# S2Mn10.net
KiCad netlist of a schematic drawn in EAGLE
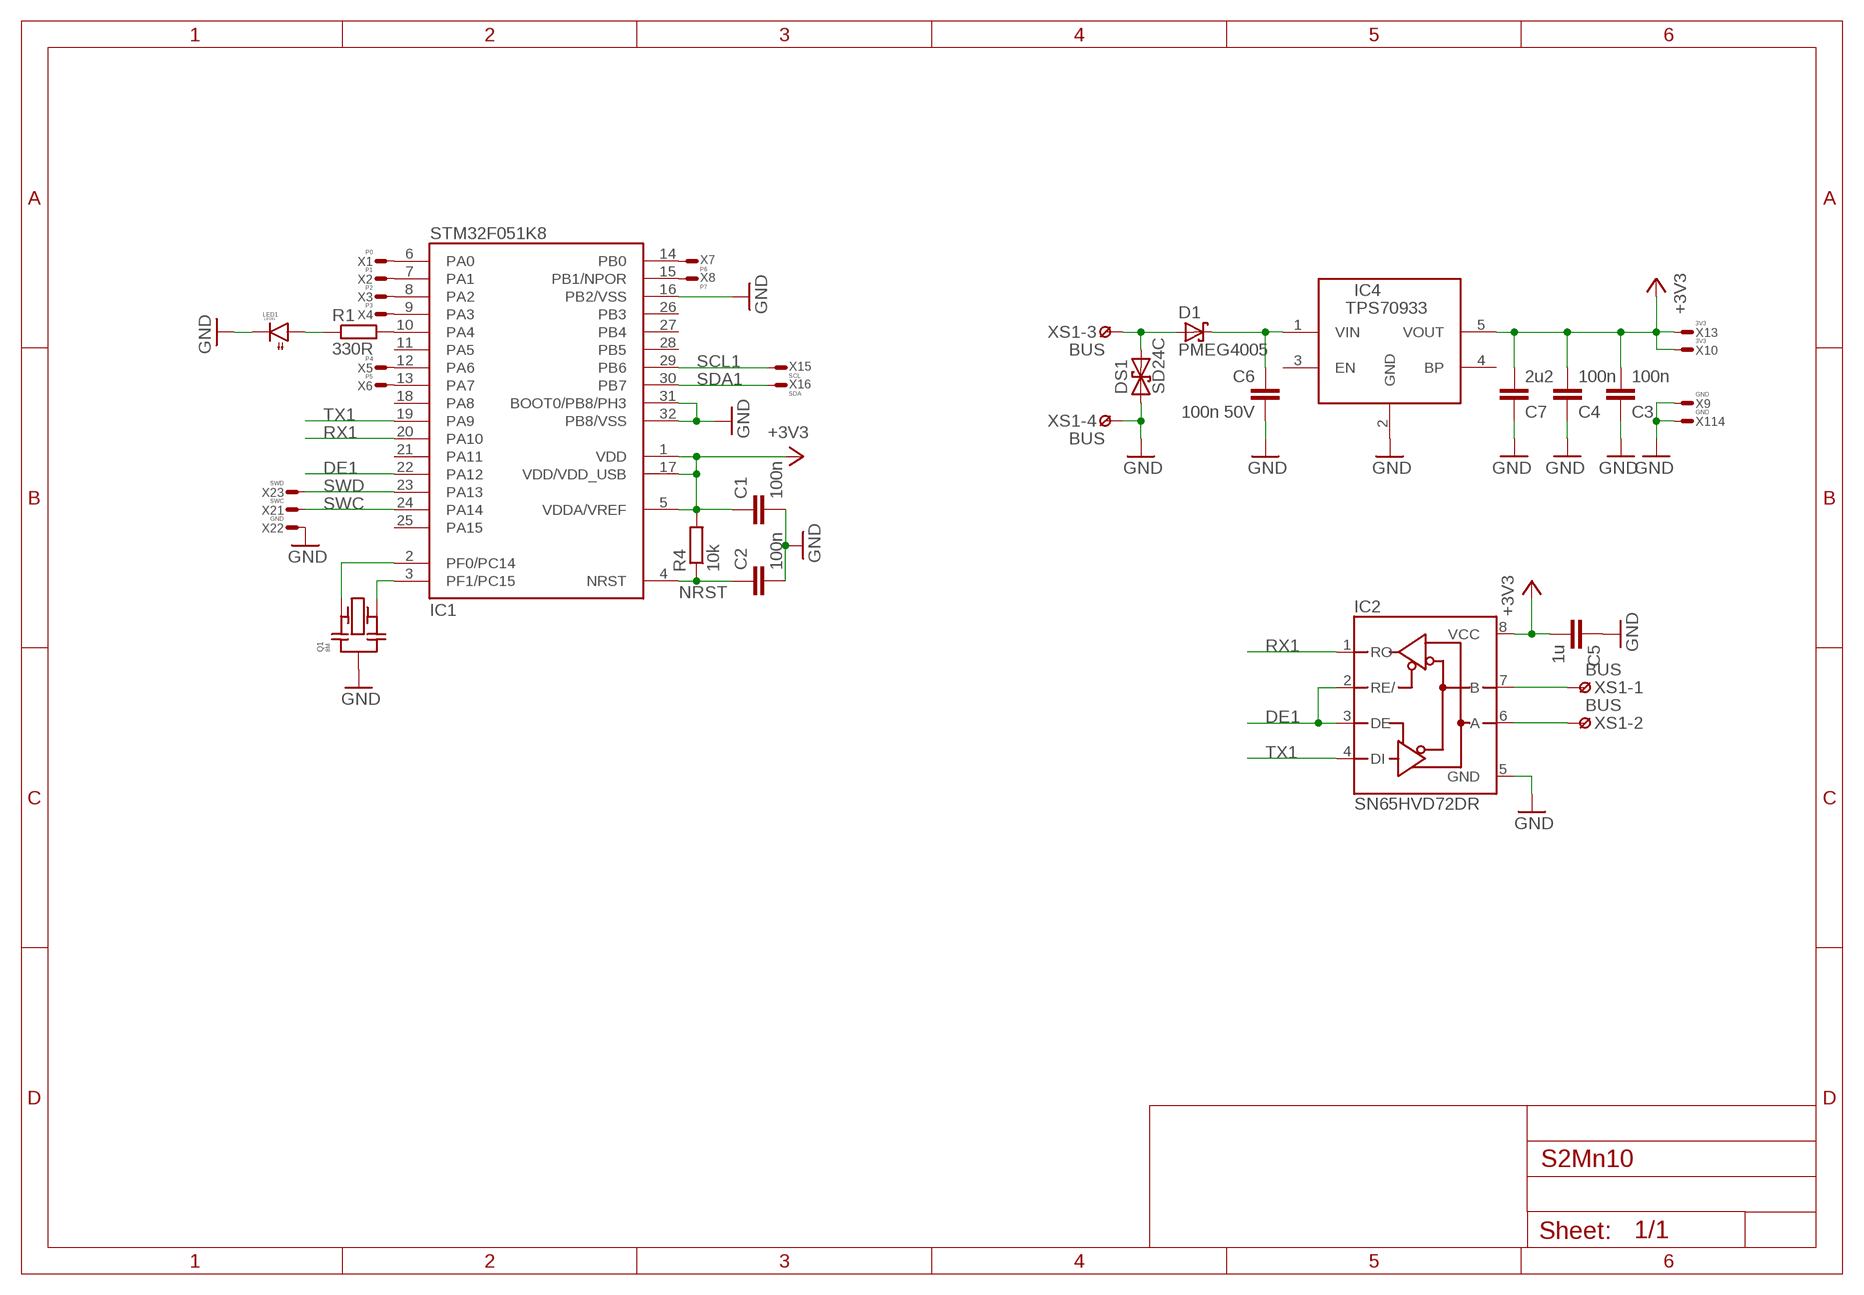
[diagram p0: schematic, sheet 1]

(export (version "E")
  (design (tool "Eeschema 10.0.6"))
  (components
    (comp (ref "C1")
      (value "100n")
      (footprint "eagle-import:0603")
      (libsource (lib "eagle-import") (part "C0603"))
    )
    (comp (ref "C2")
      (value "100n")
      (footprint "eagle-import:0603")
      (libsource (lib "eagle-import") (part "C0603"))
    )
    (comp (ref "C3")
      (value "100n")
      (footprint "eagle-import:0603")
      (libsource (lib "eagle-import") (part "C0603"))
    )
    (comp (ref "C4")
      (value "100n")
      (footprint "eagle-import:0603")
      (libsource (lib "eagle-import") (part "C0603"))
    )
    (comp (ref "C5")
      (value "1u")
      (footprint "eagle-import:0603")
      (libsource (lib "eagle-import") (part "C0603"))
    )
    (comp (ref "C6")
      (value "100n 50V")
      (footprint "eagle-import:0603")
      (libsource (lib "eagle-import") (part "C0603"))
    )
    (comp (ref "C7")
      (value "2u2")
      (footprint "eagle-import:0603")
      (libsource (lib "eagle-import") (part "C0603"))
    )
    (comp (ref "D1")
      (value "PMEG4005")
      (footprint "eagle-import:SOD323")
      (libsource (lib "eagle-import") (part "D-SCHOTKY323"))
    )
    (comp (ref "DS1")
      (value "SD24C")
      (footprint "eagle-import:SOD323")
      (libsource (lib "eagle-import") (part "TVS-U323"))
    )
    (comp (ref "IC1")
      (value "STM32F051K8")
      (footprint "eagle-import:LQFP32-7X7")
      (libsource (lib "eagle-import") (part "STM32_LQFP32"))
    )
    (comp (ref "IC2")
      (value "SN65HVD72DR")
      (footprint "eagle-import:SOIC8")
      (libsource (lib "eagle-import") (part "MAX485"))
    )
    (comp (ref "IC4")
      (value "TPS70933")
      (footprint "eagle-import:SOT23-5")
      (libsource (lib "eagle-import") (part "LDO"))
    )
    (comp (ref "LED1")
      (value "LEDG")
      (footprint "eagle-import:1206")
      (libsource (lib "eagle-import") (part "LED1206"))
    )
    (comp (ref "Q1")
      (value "8M")
      (footprint "eagle-import:CSTCE")
      (libsource (lib "eagle-import") (part "QRCE"))
    )
    (comp (ref "R1")
      (value "330R")
      (footprint "eagle-import:0603")
      (libsource (lib "eagle-import") (part "R0603"))
    )
    (comp (ref "R4")
      (value "10k")
      (footprint "eagle-import:0603")
      (libsource (lib "eagle-import") (part "R0603"))
    )
    (comp (ref "X1")
      (value "P0")
      (footprint "eagle-import:T1.6_0.9")
      (libsource (lib "eagle-import") (part "WIREPADT1.6/0.9"))
    )
    (comp (ref "X2")
      (value "P1")
      (footprint "eagle-import:T1.6_0.9")
      (libsource (lib "eagle-import") (part "WIREPADT1.6/0.9"))
    )
    (comp (ref "X3")
      (value "P2")
      (footprint "eagle-import:T1.6_0.9")
      (libsource (lib "eagle-import") (part "WIREPADT1.6/0.9"))
    )
    (comp (ref "X4")
      (value "P3")
      (footprint "eagle-import:T1.6_0.9")
      (libsource (lib "eagle-import") (part "WIREPADT1.6/0.9"))
    )
    (comp (ref "X5")
      (value "P4")
      (footprint "eagle-import:T1.6_0.9")
      (libsource (lib "eagle-import") (part "WIREPADT1.6/0.9"))
    )
    (comp (ref "X6")
      (value "P5")
      (footprint "eagle-import:T1.6_0.9")
      (libsource (lib "eagle-import") (part "WIREPADT1.6/0.9"))
    )
    (comp (ref "X7")
      (value "P6")
      (footprint "eagle-import:T1.6_0.9")
      (libsource (lib "eagle-import") (part "WIREPADT1.6/0.9"))
    )
    (comp (ref "X8")
      (value "P7")
      (footprint "eagle-import:T1.6_0.9")
      (libsource (lib "eagle-import") (part "WIREPADT1.6/0.9"))
    )
    (comp (ref "X9")
      (value "GND")
      (footprint "eagle-import:T1.6_0.9")
      (libsource (lib "eagle-import") (part "WIREPADT1.6/0.9"))
    )
    (comp (ref "X10")
      (value "3V3")
      (footprint "eagle-import:T1.6_0.9")
      (libsource (lib "eagle-import") (part "WIREPADT1.6/0.9"))
    )
    (comp (ref "X13")
      (value "3V3")
      (footprint "eagle-import:T1.6_0.9")
      (libsource (lib "eagle-import") (part "WIREPADT1.6/0.9"))
    )
    (comp (ref "X15")
      (value "SCL")
      (footprint "eagle-import:T1.6_0.9")
      (libsource (lib "eagle-import") (part "WIREPADT1.6/0.9"))
    )
    (comp (ref "X16")
      (value "SDA")
      (footprint "eagle-import:T1.6_0.9")
      (libsource (lib "eagle-import") (part "WIREPADT1.6/0.9"))
    )
    (comp (ref "X21")
      (value "SWC")
      (footprint "eagle-import:T1.6_0.9")
      (libsource (lib "eagle-import") (part "WIREPADT1.6/0.9"))
    )
    (comp (ref "X22")
      (value "GND")
      (footprint "eagle-import:T1.6_0.9")
      (libsource (lib "eagle-import") (part "WIREPADT1.6/0.9"))
    )
    (comp (ref "X23")
      (value "SWD")
      (footprint "eagle-import:T1.6_0.9")
      (libsource (lib "eagle-import") (part "WIREPADT1.6/0.9"))
    )
    (comp (ref "X114")
      (value "GND")
      (footprint "eagle-import:T1.6_0.9")
      (libsource (lib "eagle-import") (part "WIREPADT1.6/0.9"))
    )
    (comp (ref "XS1")
      (value "BUS")
      (footprint "eagle-import:1725672")
      (libsource (lib "eagle-import") (part "1725672"))
    )
  )
  (nets
    (net (code "1") (name "+3V3") (class "Default")
      (node (ref "C1") (pin "1") (pinfunction "1_1") (pintype "passive"))
      (node (ref "C3") (pin "2") (pinfunction "2_2") (pintype "passive"))
      (node (ref "C4") (pin "2") (pinfunction "2_2") (pintype "passive"))
      (node (ref "C5") (pin "2") (pinfunction "2_2") (pintype "passive"))
      (node (ref "C7") (pin "2") (pinfunction "2_2") (pintype "passive"))
      (node (ref "IC1") (pin "1") (pinfunction "VDD_1") (pintype "bidirectional"))
      (node (ref "IC1") (pin "17") (pinfunction "VDD/VDD_USB_17") (pintype "bidirectional"))
      (node (ref "IC1") (pin "5") (pinfunction "VDDA/VREF_5") (pintype "bidirectional"))
      (node (ref "IC2") (pin "8") (pinfunction "VCC_8") (pintype "bidirectional"))
      (node (ref "IC4") (pin "5") (pinfunction "VOUT_5") (pintype "bidirectional"))
      (node (ref "R4") (pin "2") (pinfunction "2_2") (pintype "passive"))
      (node (ref "X10") (pin "1") (pinfunction "S_1") (pintype "passive"))
      (node (ref "X13") (pin "1") (pinfunction "S_1") (pintype "passive"))
    )
    (net (code "2") (name "/DE1") (class "Default")
      (node (ref "IC1") (pin "22") (pinfunction "PA12_22") (pintype "bidirectional"))
      (node (ref "IC2") (pin "2") (pinfunction "RE/_2") (pintype "bidirectional"))
      (node (ref "IC2") (pin "3") (pinfunction "DE_3") (pintype "bidirectional"))
    )
    (net (code "3") (name "/NRST") (class "Default")
      (node (ref "C2") (pin "1") (pinfunction "1_1") (pintype "passive"))
      (node (ref "IC1") (pin "4") (pinfunction "NRST_4") (pintype "bidirectional"))
      (node (ref "R4") (pin "1") (pinfunction "1_1") (pintype "passive"))
    )
    (net (code "4") (name "/RX1") (class "Default")
      (node (ref "IC1") (pin "20") (pinfunction "PA10_20") (pintype "bidirectional"))
      (node (ref "IC2") (pin "1") (pinfunction "RO_1") (pintype "bidirectional"))
    )
    (net (code "5") (name "/SCL1") (class "Default")
      (node (ref "IC1") (pin "29") (pinfunction "PB6_29") (pintype "bidirectional"))
      (node (ref "X15") (pin "1") (pinfunction "S_1") (pintype "passive"))
    )
    (net (code "6") (name "/SDA1") (class "Default")
      (node (ref "IC1") (pin "30") (pinfunction "PB7_30") (pintype "bidirectional"))
      (node (ref "X16") (pin "1") (pinfunction "S_1") (pintype "passive"))
    )
    (net (code "7") (name "/SWC") (class "Default")
      (node (ref "IC1") (pin "24") (pinfunction "PA14_24") (pintype "bidirectional"))
      (node (ref "X21") (pin "1") (pinfunction "S_1") (pintype "passive"))
    )
    (net (code "8") (name "/SWD") (class "Default")
      (node (ref "IC1") (pin "23") (pinfunction "PA13_23") (pintype "bidirectional"))
      (node (ref "X23") (pin "1") (pinfunction "S_1") (pintype "passive"))
    )
    (net (code "9") (name "/TX1") (class "Default")
      (node (ref "IC1") (pin "19") (pinfunction "PA9_19") (pintype "bidirectional"))
      (node (ref "IC2") (pin "4") (pinfunction "DI_4") (pintype "bidirectional"))
    )
    (net (code "10") (name "GND") (class "Default")
      (node (ref "C1") (pin "2") (pinfunction "2_2") (pintype "passive"))
      (node (ref "C2") (pin "2") (pinfunction "2_2") (pintype "passive"))
      (node (ref "C3") (pin "1") (pinfunction "1_1") (pintype "passive"))
      (node (ref "C4") (pin "1") (pinfunction "1_1") (pintype "passive"))
      (node (ref "C5") (pin "1") (pinfunction "1_1") (pintype "passive"))
      (node (ref "C6") (pin "2") (pinfunction "2_2") (pintype "passive"))
      (node (ref "C7") (pin "1") (pinfunction "1_1") (pintype "passive"))
      (node (ref "DS1") (pin "A") (pinfunction "1_A") (pintype "passive"))
      (node (ref "IC1") (pin "16") (pinfunction "PB2/VSS_16") (pintype "bidirectional"))
      (node (ref "IC1") (pin "31") (pinfunction "BOOT0/PB8/PH3_31") (pintype "bidirectional"))
      (node (ref "IC1") (pin "32") (pinfunction "PB8/VSS_32") (pintype "bidirectional"))
      (node (ref "IC2") (pin "5") (pinfunction "GND_5") (pintype "bidirectional"))
      (node (ref "IC4") (pin "2") (pinfunction "GND_2") (pintype "bidirectional"))
      (node (ref "LED1") (pin "2") (pinfunction "C_2") (pintype "bidirectional"))
      (node (ref "Q1") (pin "G") (pinfunction "M_G") (pintype "passive"))
      (node (ref "X114") (pin "1") (pinfunction "S_1") (pintype "passive"))
      (node (ref "X22") (pin "1") (pinfunction "S_1") (pintype "passive"))
      (node (ref "X9") (pin "1") (pinfunction "S_1") (pintype "passive"))
      (node (ref "XS1") (pin "4") (pinfunction "K_4") (pintype "passive"))
    )
    (net (code "11") (name "Net-(DS1-2)") (class "Default")
      (node (ref "D1") (pin "A") (pinfunction "A_A") (pintype "passive"))
      (node (ref "DS1") (pin "C") (pinfunction "2_C") (pintype "passive"))
      (node (ref "XS1") (pin "3") (pinfunction "K_3") (pintype "passive"))
    )
    (net (code "12") (name "Net-(IC1-PA0)") (class "Default")
      (node (ref "IC1") (pin "6") (pinfunction "PA0_6") (pintype "bidirectional"))
      (node (ref "X1") (pin "1") (pinfunction "S_1") (pintype "passive"))
    )
    (net (code "13") (name "Net-(IC1-PA1)") (class "Default")
      (node (ref "IC1") (pin "7") (pinfunction "PA1_7") (pintype "bidirectional"))
      (node (ref "X2") (pin "1") (pinfunction "S_1") (pintype "passive"))
    )
    (net (code "14") (name "Net-(IC1-PA2)") (class "Default")
      (node (ref "IC1") (pin "8") (pinfunction "PA2_8") (pintype "bidirectional"))
      (node (ref "X3") (pin "1") (pinfunction "S_1") (pintype "passive"))
    )
    (net (code "15") (name "Net-(IC1-PA3)") (class "Default")
      (node (ref "IC1") (pin "9") (pinfunction "PA3_9") (pintype "bidirectional"))
      (node (ref "X4") (pin "1") (pinfunction "S_1") (pintype "passive"))
    )
    (net (code "16") (name "Net-(IC1-PA4)") (class "Default")
      (node (ref "IC1") (pin "10") (pinfunction "PA4_10") (pintype "bidirectional"))
      (node (ref "R1") (pin "2") (pinfunction "2_2") (pintype "passive"))
    )
    (net (code "17") (name "Net-(IC1-PA6)") (class "Default")
      (node (ref "IC1") (pin "12") (pinfunction "PA6_12") (pintype "bidirectional"))
      (node (ref "X5") (pin "1") (pinfunction "S_1") (pintype "passive"))
    )
    (net (code "18") (name "Net-(IC1-PA7)") (class "Default")
      (node (ref "IC1") (pin "13") (pinfunction "PA7_13") (pintype "bidirectional"))
      (node (ref "X6") (pin "1") (pinfunction "S_1") (pintype "passive"))
    )
    (net (code "19") (name "Net-(IC1-PB0)") (class "Default")
      (node (ref "IC1") (pin "14") (pinfunction "PB0_14") (pintype "bidirectional"))
      (node (ref "X7") (pin "1") (pinfunction "S_1") (pintype "passive"))
    )
    (net (code "20") (name "Net-(IC1-PB1{slash}NPOR)") (class "Default")
      (node (ref "IC1") (pin "15") (pinfunction "PB1/NPOR_15") (pintype "bidirectional"))
      (node (ref "X8") (pin "1") (pinfunction "S_1") (pintype "passive"))
    )
    (net (code "21") (name "Net-(IC1-PF0{slash}PC14)") (class "Default")
      (node (ref "IC1") (pin "2") (pinfunction "PF0/PC14_2") (pintype "bidirectional"))
      (node (ref "Q1") (pin "A") (pinfunction "1_A") (pintype "passive"))
    )
    (net (code "22") (name "Net-(IC1-PF1{slash}PC15)") (class "Default")
      (node (ref "IC1") (pin "3") (pinfunction "PF1/PC15_3") (pintype "bidirectional"))
      (node (ref "Q1") (pin "B") (pinfunction "2_B") (pintype "passive"))
    )
    (net (code "23") (name "Net-(IC2-A)") (class "Default")
      (node (ref "IC2") (pin "6") (pinfunction "A_6") (pintype "bidirectional"))
      (node (ref "XS1") (pin "2") (pinfunction "K_2") (pintype "passive"))
    )
    (net (code "24") (name "Net-(IC2-B)") (class "Default")
      (node (ref "IC2") (pin "7") (pinfunction "B_7") (pintype "bidirectional"))
      (node (ref "XS1") (pin "1") (pinfunction "K_1") (pintype "passive"))
    )
    (net (code "25") (name "Net-(IC4-VIN)") (class "Default")
      (node (ref "C6") (pin "1") (pinfunction "1_1") (pintype "passive"))
      (node (ref "D1") (pin "C") (pinfunction "C_C") (pintype "passive"))
      (node (ref "IC4") (pin "1") (pinfunction "VIN_1") (pintype "bidirectional"))
    )
    (net (code "26") (name "Net-(LED1-A)") (class "Default")
      (node (ref "LED1") (pin "1") (pinfunction "A_1") (pintype "bidirectional"))
      (node (ref "R1") (pin "1") (pinfunction "1_1") (pintype "passive"))
    )
    (net (code "27") (name "unconnected-(IC1-PA5-Pad11)") (class "Default")
      (node (ref "IC1") (pin "11") (pinfunction "PA5_11") (pintype "bidirectional"))
    )
    (net (code "28") (name "unconnected-(IC1-PA8-Pad18)") (class "Default")
      (node (ref "IC1") (pin "18") (pinfunction "PA8_18") (pintype "bidirectional"))
    )
    (net (code "29") (name "unconnected-(IC1-PA11-Pad21)") (class "Default")
      (node (ref "IC1") (pin "21") (pinfunction "PA11_21") (pintype "bidirectional"))
    )
    (net (code "30") (name "unconnected-(IC1-PA15-Pad25)") (class "Default")
      (node (ref "IC1") (pin "25") (pinfunction "PA15_25") (pintype "bidirectional"))
    )
    (net (code "31") (name "unconnected-(IC1-PB3-Pad26)") (class "Default")
      (node (ref "IC1") (pin "26") (pinfunction "PB3_26") (pintype "bidirectional"))
    )
    (net (code "32") (name "unconnected-(IC1-PB4-Pad27)") (class "Default")
      (node (ref "IC1") (pin "27") (pinfunction "PB4_27") (pintype "bidirectional"))
    )
    (net (code "33") (name "unconnected-(IC1-PB5-Pad28)") (class "Default")
      (node (ref "IC1") (pin "28") (pinfunction "PB5_28") (pintype "bidirectional"))
    )
    (net (code "34") (name "unconnected-(IC4-BP-Pad4)") (class "Default")
      (node (ref "IC4") (pin "4") (pinfunction "BP_4") (pintype "bidirectional"))
    )
    (net (code "35") (name "unconnected-(IC4-EN-Pad3)") (class "Default")
      (node (ref "IC4") (pin "3") (pinfunction "EN_3") (pintype "bidirectional"))
    )
  )
)
